# fpc.net
KiCad netlist of a schematic drawn in Altium Designer
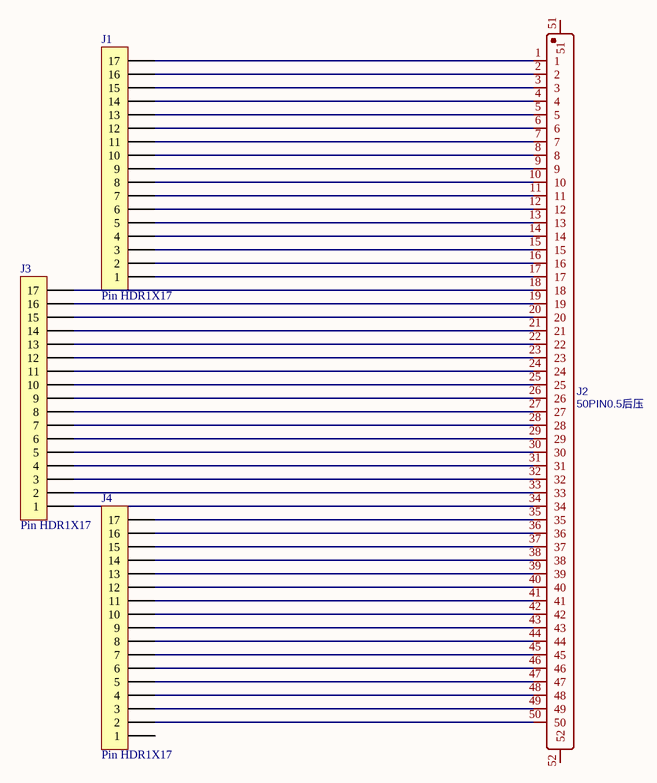
[diagram p0: fpc.SchDoc]

(export (version "E")
  (design (tool "Eeschema 10.0.6"))
  (components
    (comp (ref "J1")
      (value "Pin HDR1X17")
      (footprint "Pin HDR1X17/2.54mm-S")
      (libsource (lib "常用元件-排针") (part "Pin HDR1X17"))
    )
    (comp (ref "J2")
      (value "50PIN0.5后压")
      (footprint "FPC-SMD_KH-FG0.5-H2.0-50PIN")
      (fields (field (name "BOM_SUPPLIER PART") "C9900011403") (field (name "CONTRIBUTOR") "LCSC"))
      (libsource (lib "altium-import") (part "root_0_50PIN0.5后压_"))
    )
    (comp (ref "J3")
      (value "Pin HDR1X17")
      (footprint "Pin HDR1X17/2.54mm-S")
      (libsource (lib "常用元件-排针") (part "Pin HDR1X17"))
    )
    (comp (ref "J4")
      (value "Pin HDR1X17")
      (footprint "Pin HDR1X17/2.54mm-S")
      (libsource (lib "常用元件-排针") (part "Pin HDR1X17"))
    )
  )
  (nets
    (net (code "1") (name "Net-(J1-Pad1)") (class "Default")
      (node (ref "J1") (pin "1") (pinfunction "1_1") (pintype "passive"))
      (node (ref "J2") (pin "17") (pinfunction "17_17") (pintype "passive"))
    )
    (net (code "2") (name "Net-(J1-Pad2)") (class "Default")
      (node (ref "J1") (pin "2") (pinfunction "2_2") (pintype "passive"))
      (node (ref "J2") (pin "16") (pinfunction "16_16") (pintype "passive"))
    )
    (net (code "3") (name "Net-(J1-Pad3)") (class "Default")
      (node (ref "J1") (pin "3") (pinfunction "3_3") (pintype "passive"))
      (node (ref "J2") (pin "15") (pinfunction "15_15") (pintype "passive"))
    )
    (net (code "4") (name "Net-(J1-Pad4)") (class "Default")
      (node (ref "J1") (pin "4") (pinfunction "4_4") (pintype "passive"))
      (node (ref "J2") (pin "14") (pinfunction "14_14") (pintype "passive"))
    )
    (net (code "5") (name "Net-(J1-Pad5)") (class "Default")
      (node (ref "J1") (pin "5") (pinfunction "5_5") (pintype "passive"))
      (node (ref "J2") (pin "13") (pinfunction "13_13") (pintype "passive"))
    )
    (net (code "6") (name "Net-(J1-Pad6)") (class "Default")
      (node (ref "J1") (pin "6") (pinfunction "6_6") (pintype "passive"))
      (node (ref "J2") (pin "12") (pinfunction "12_12") (pintype "passive"))
    )
    (net (code "7") (name "Net-(J1-Pad7)") (class "Default")
      (node (ref "J1") (pin "7") (pinfunction "7_7") (pintype "passive"))
      (node (ref "J2") (pin "11") (pinfunction "11_11") (pintype "passive"))
    )
    (net (code "8") (name "Net-(J1-Pad8)") (class "Default")
      (node (ref "J1") (pin "8") (pinfunction "8_8") (pintype "passive"))
      (node (ref "J2") (pin "10") (pinfunction "10_10") (pintype "passive"))
    )
    (net (code "9") (name "Net-(J1-Pad9)") (class "Default")
      (node (ref "J1") (pin "9") (pinfunction "9_9") (pintype "passive"))
      (node (ref "J2") (pin "9") (pinfunction "9_9") (pintype "passive"))
    )
    (net (code "10") (name "Net-(J1-Pad10)") (class "Default")
      (node (ref "J1") (pin "10") (pinfunction "10_10") (pintype "passive"))
      (node (ref "J2") (pin "8") (pinfunction "8_8") (pintype "passive"))
    )
    (net (code "11") (name "Net-(J1-Pad11)") (class "Default")
      (node (ref "J1") (pin "11") (pinfunction "11_11") (pintype "passive"))
      (node (ref "J2") (pin "7") (pinfunction "7_7") (pintype "passive"))
    )
    (net (code "12") (name "Net-(J1-Pad12)") (class "Default")
      (node (ref "J1") (pin "12") (pinfunction "12_12") (pintype "passive"))
      (node (ref "J2") (pin "6") (pinfunction "6_6") (pintype "passive"))
    )
    (net (code "13") (name "Net-(J1-Pad13)") (class "Default")
      (node (ref "J1") (pin "13") (pinfunction "13_13") (pintype "passive"))
      (node (ref "J2") (pin "5") (pinfunction "5_5") (pintype "passive"))
    )
    (net (code "14") (name "Net-(J1-Pad14)") (class "Default")
      (node (ref "J1") (pin "14") (pinfunction "14_14") (pintype "passive"))
      (node (ref "J2") (pin "4") (pinfunction "4_4") (pintype "passive"))
    )
    (net (code "15") (name "Net-(J1-Pad15)") (class "Default")
      (node (ref "J1") (pin "15") (pinfunction "15_15") (pintype "passive"))
      (node (ref "J2") (pin "3") (pinfunction "3_3") (pintype "passive"))
    )
    (net (code "16") (name "Net-(J1-Pad16)") (class "Default")
      (node (ref "J1") (pin "16") (pinfunction "16_16") (pintype "passive"))
      (node (ref "J2") (pin "2") (pinfunction "2_2") (pintype "passive"))
    )
    (net (code "17") (name "Net-(J1-Pad17)") (class "Default")
      (node (ref "J1") (pin "17") (pinfunction "17_17") (pintype "passive"))
      (node (ref "J2") (pin "1") (pinfunction "1_1") (pintype "passive"))
    )
    (net (code "18") (name "Net-(J2-Pad18)") (class "Default")
      (node (ref "J2") (pin "18") (pinfunction "18_18") (pintype "passive"))
      (node (ref "J3") (pin "17") (pinfunction "17_17") (pintype "passive"))
    )
    (net (code "19") (name "Net-(J2-Pad19)") (class "Default")
      (node (ref "J2") (pin "19") (pinfunction "19_19") (pintype "passive"))
      (node (ref "J3") (pin "16") (pinfunction "16_16") (pintype "passive"))
    )
    (net (code "20") (name "Net-(J2-Pad20)") (class "Default")
      (node (ref "J2") (pin "20") (pinfunction "20_20") (pintype "passive"))
      (node (ref "J3") (pin "15") (pinfunction "15_15") (pintype "passive"))
    )
    (net (code "21") (name "Net-(J2-Pad21)") (class "Default")
      (node (ref "J2") (pin "21") (pinfunction "21_21") (pintype "passive"))
      (node (ref "J3") (pin "14") (pinfunction "14_14") (pintype "passive"))
    )
    (net (code "22") (name "Net-(J2-Pad22)") (class "Default")
      (node (ref "J2") (pin "22") (pinfunction "22_22") (pintype "passive"))
      (node (ref "J3") (pin "13") (pinfunction "13_13") (pintype "passive"))
    )
    (net (code "23") (name "Net-(J2-Pad23)") (class "Default")
      (node (ref "J2") (pin "23") (pinfunction "23_23") (pintype "passive"))
      (node (ref "J3") (pin "12") (pinfunction "12_12") (pintype "passive"))
    )
    (net (code "24") (name "Net-(J2-Pad24)") (class "Default")
      (node (ref "J2") (pin "24") (pinfunction "24_24") (pintype "passive"))
      (node (ref "J3") (pin "11") (pinfunction "11_11") (pintype "passive"))
    )
    (net (code "25") (name "Net-(J2-Pad25)") (class "Default")
      (node (ref "J2") (pin "25") (pinfunction "25_25") (pintype "passive"))
      (node (ref "J3") (pin "10") (pinfunction "10_10") (pintype "passive"))
    )
    (net (code "26") (name "Net-(J2-Pad26)") (class "Default")
      (node (ref "J2") (pin "26") (pinfunction "26_26") (pintype "passive"))
      (node (ref "J3") (pin "9") (pinfunction "9_9") (pintype "passive"))
    )
    (net (code "27") (name "Net-(J2-Pad27)") (class "Default")
      (node (ref "J2") (pin "27") (pinfunction "27_27") (pintype "passive"))
      (node (ref "J3") (pin "8") (pinfunction "8_8") (pintype "passive"))
    )
    (net (code "28") (name "Net-(J2-Pad28)") (class "Default")
      (node (ref "J2") (pin "28") (pinfunction "28_28") (pintype "passive"))
      (node (ref "J3") (pin "7") (pinfunction "7_7") (pintype "passive"))
    )
    (net (code "29") (name "Net-(J2-Pad29)") (class "Default")
      (node (ref "J2") (pin "29") (pinfunction "29_29") (pintype "passive"))
      (node (ref "J3") (pin "6") (pinfunction "6_6") (pintype "passive"))
    )
    (net (code "30") (name "Net-(J2-Pad30)") (class "Default")
      (node (ref "J2") (pin "30") (pinfunction "30_30") (pintype "passive"))
      (node (ref "J3") (pin "5") (pinfunction "5_5") (pintype "passive"))
    )
    (net (code "31") (name "Net-(J2-Pad31)") (class "Default")
      (node (ref "J2") (pin "31") (pinfunction "31_31") (pintype "passive"))
      (node (ref "J3") (pin "4") (pinfunction "4_4") (pintype "passive"))
    )
    (net (code "32") (name "Net-(J2-Pad32)") (class "Default")
      (node (ref "J2") (pin "32") (pinfunction "32_32") (pintype "passive"))
      (node (ref "J3") (pin "3") (pinfunction "3_3") (pintype "passive"))
    )
    (net (code "33") (name "Net-(J2-Pad33)") (class "Default")
      (node (ref "J2") (pin "33") (pinfunction "33_33") (pintype "passive"))
      (node (ref "J3") (pin "2") (pinfunction "2_2") (pintype "passive"))
    )
    (net (code "34") (name "Net-(J2-Pad34)") (class "Default")
      (node (ref "J2") (pin "34") (pinfunction "34_34") (pintype "passive"))
      (node (ref "J3") (pin "1") (pinfunction "1_1") (pintype "passive"))
    )
    (net (code "35") (name "Net-(J2-Pad35)") (class "Default")
      (node (ref "J2") (pin "35") (pinfunction "35_35") (pintype "passive"))
      (node (ref "J4") (pin "17") (pinfunction "17_17") (pintype "passive"))
    )
    (net (code "36") (name "Net-(J2-Pad36)") (class "Default")
      (node (ref "J2") (pin "36") (pinfunction "36_36") (pintype "passive"))
      (node (ref "J4") (pin "16") (pinfunction "16_16") (pintype "passive"))
    )
    (net (code "37") (name "Net-(J2-Pad37)") (class "Default")
      (node (ref "J2") (pin "37") (pinfunction "37_37") (pintype "passive"))
      (node (ref "J4") (pin "15") (pinfunction "15_15") (pintype "passive"))
    )
    (net (code "38") (name "Net-(J2-Pad38)") (class "Default")
      (node (ref "J2") (pin "38") (pinfunction "38_38") (pintype "passive"))
      (node (ref "J4") (pin "14") (pinfunction "14_14") (pintype "passive"))
    )
    (net (code "39") (name "Net-(J2-Pad39)") (class "Default")
      (node (ref "J2") (pin "39") (pinfunction "39_39") (pintype "passive"))
      (node (ref "J4") (pin "13") (pinfunction "13_13") (pintype "passive"))
    )
    (net (code "40") (name "Net-(J2-Pad40)") (class "Default")
      (node (ref "J2") (pin "40") (pinfunction "40_40") (pintype "passive"))
      (node (ref "J4") (pin "12") (pinfunction "12_12") (pintype "passive"))
    )
    (net (code "41") (name "Net-(J2-Pad41)") (class "Default")
      (node (ref "J2") (pin "41") (pinfunction "41_41") (pintype "passive"))
      (node (ref "J4") (pin "11") (pinfunction "11_11") (pintype "passive"))
    )
    (net (code "42") (name "Net-(J2-Pad42)") (class "Default")
      (node (ref "J2") (pin "42") (pinfunction "42_42") (pintype "passive"))
      (node (ref "J4") (pin "10") (pinfunction "10_10") (pintype "passive"))
    )
    (net (code "43") (name "Net-(J2-Pad43)") (class "Default")
      (node (ref "J2") (pin "43") (pinfunction "43_43") (pintype "passive"))
      (node (ref "J4") (pin "9") (pinfunction "9_9") (pintype "passive"))
    )
    (net (code "44") (name "Net-(J2-Pad44)") (class "Default")
      (node (ref "J2") (pin "44") (pinfunction "44_44") (pintype "passive"))
      (node (ref "J4") (pin "8") (pinfunction "8_8") (pintype "passive"))
    )
    (net (code "45") (name "Net-(J2-Pad45)") (class "Default")
      (node (ref "J2") (pin "45") (pinfunction "45_45") (pintype "passive"))
      (node (ref "J4") (pin "7") (pinfunction "7_7") (pintype "passive"))
    )
    (net (code "46") (name "Net-(J2-Pad46)") (class "Default")
      (node (ref "J2") (pin "46") (pinfunction "46_46") (pintype "passive"))
      (node (ref "J4") (pin "6") (pinfunction "6_6") (pintype "passive"))
    )
    (net (code "47") (name "Net-(J2-Pad47)") (class "Default")
      (node (ref "J2") (pin "47") (pinfunction "47_47") (pintype "passive"))
      (node (ref "J4") (pin "5") (pinfunction "5_5") (pintype "passive"))
    )
    (net (code "48") (name "Net-(J2-Pad48)") (class "Default")
      (node (ref "J2") (pin "48") (pinfunction "48_48") (pintype "passive"))
      (node (ref "J4") (pin "4") (pinfunction "4_4") (pintype "passive"))
    )
    (net (code "49") (name "Net-(J2-Pad49)") (class "Default")
      (node (ref "J2") (pin "49") (pinfunction "49_49") (pintype "passive"))
      (node (ref "J4") (pin "3") (pinfunction "3_3") (pintype "passive"))
    )
    (net (code "50") (name "Net-(J2-Pad50)") (class "Default")
      (node (ref "J2") (pin "50") (pinfunction "50_50") (pintype "passive"))
      (node (ref "J4") (pin "2") (pinfunction "2_2") (pintype "passive"))
    )
    (net (code "51") (name "unconnected-(J2-Pad51)") (class "Default")
      (node (ref "J2") (pin "51") (pinfunction "51_51") (pintype "passive"))
    )
    (net (code "52") (name "unconnected-(J2-Pad52)") (class "Default")
      (node (ref "J2") (pin "52") (pinfunction "52_52") (pintype "passive"))
    )
    (net (code "53") (name "unconnected-(J4-Pad1)") (class "Default")
      (node (ref "J4") (pin "1") (pinfunction "1_1") (pintype "passive"))
    )
  )
)
